# relay_shield3a.net
KiCad netlist of a schematic drawn in EAGLE
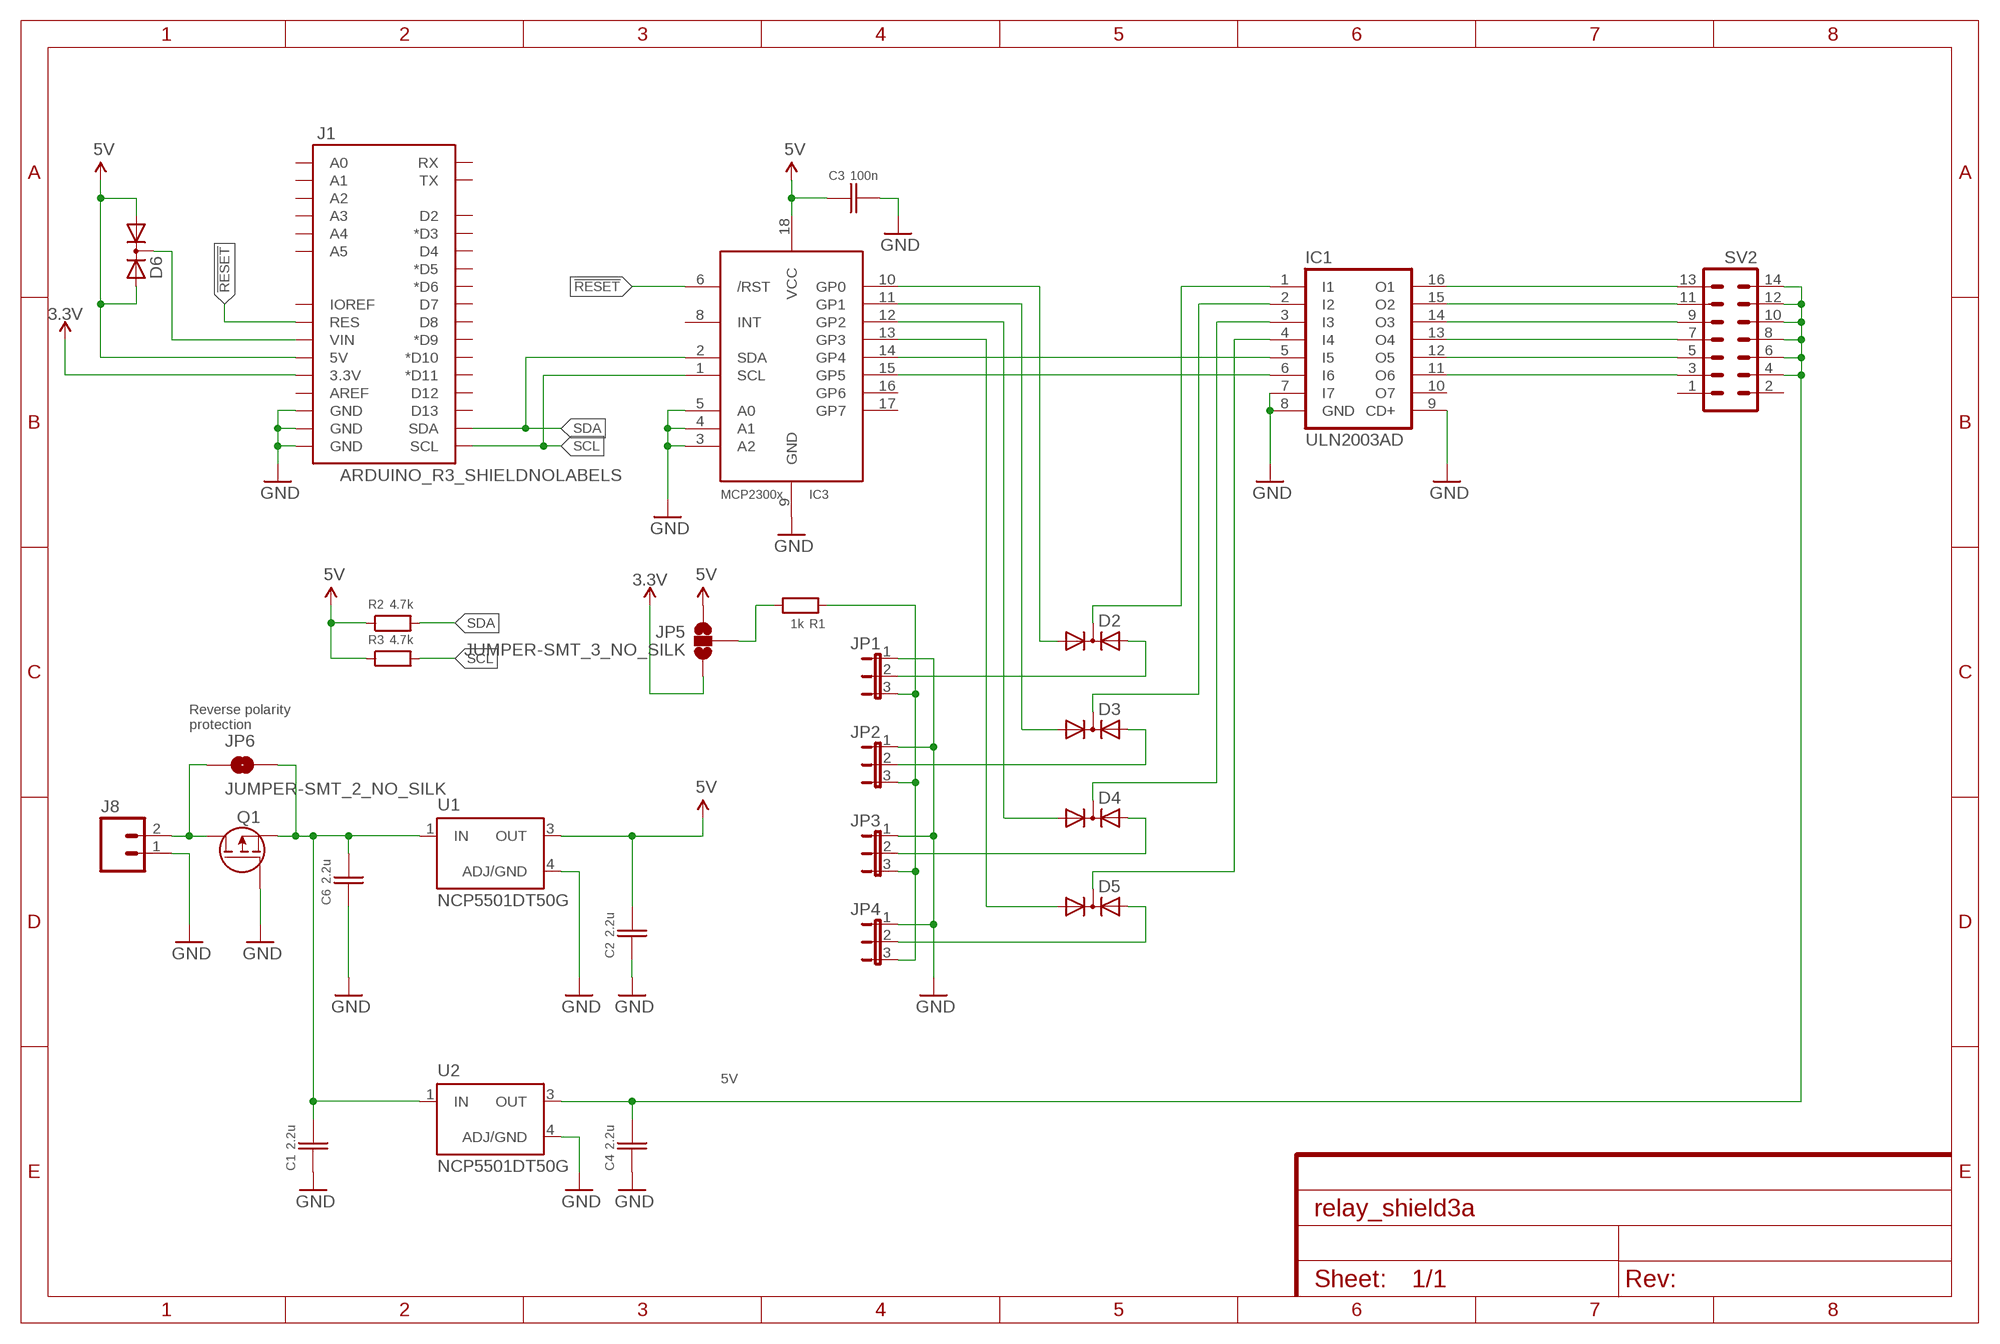
[diagram p0: schematic, sheet 1]

(export (version "E")
  (design (tool "Eeschema 10.0.6"))
  (components
    (comp (ref "C1")
      (value "2.2u")
      (footprint "eagle-import:C1206")
      (libsource (lib "eagle-import") (part "CAPACITOR_NPOL-1206"))
    )
    (comp (ref "C2")
      (value "2.2u")
      (footprint "eagle-import:C1206")
      (libsource (lib "eagle-import") (part "CAPACITOR_NPOL-1206"))
    )
    (comp (ref "C3")
      (value "100n")
      (footprint "eagle-import:C603")
      (libsource (lib "eagle-import") (part "CAPACITOR_NPOL-0603"))
    )
    (comp (ref "C4")
      (value "2.2u")
      (footprint "eagle-import:C1206")
      (libsource (lib "eagle-import") (part "CAPACITOR_NPOL-1206"))
    )
    (comp (ref "C6")
      (value "2.2u")
      (footprint "eagle-import:C1206")
      (libsource (lib "eagle-import") (part "CAPACITOR_NPOL-1206"))
    )
    (comp (ref "D2")
      (value "DIODE-2AC|CASOT23")
      (footprint "eagle-import:SOT23")
      (libsource (lib "eagle-import") (part "DIODE-2AC|CASOT23"))
    )
    (comp (ref "D3")
      (value "DIODE-2AC|CASOT23")
      (footprint "eagle-import:SOT23")
      (libsource (lib "eagle-import") (part "DIODE-2AC|CASOT23"))
    )
    (comp (ref "D4")
      (value "DIODE-2AC|CASOT23")
      (footprint "eagle-import:SOT23")
      (libsource (lib "eagle-import") (part "DIODE-2AC|CASOT23"))
    )
    (comp (ref "D5")
      (value "DIODE-2AC|CASOT23")
      (footprint "eagle-import:SOT23")
      (libsource (lib "eagle-import") (part "DIODE-2AC|CASOT23"))
    )
    (comp (ref "D6")
      (value "DIODE-2AC|CASOT23")
      (footprint "eagle-import:SOT23")
      (libsource (lib "eagle-import") (part "DIODE-2AC|CASOT23"))
    )
    (comp (ref "IC1")
      (value "ULN2003AD")
      (footprint "eagle-import:SO16")
      (libsource (lib "eagle-import") (part "ULN2003AD"))
    )
    (comp (ref "IC3")
      (value "MCP23008/SO")
      (footprint "eagle-import:SO18W")
      (libsource (lib "eagle-import") (part "MCP23008/SO"))
    )
    (comp (ref "J1")
      (value "ARDUINO_R3_SHIELDNOLABELS")
      (footprint "eagle-import:UNO_R3_SHIELD_NOLABELS")
      (libsource (lib "eagle-import") (part "ARDUINO_R3_SHIELDNOLABELS"))
    )
    (comp (ref "J8")
      (value "M023.5MM")
      (footprint "eagle-import:SCREWTERMINAL-3.5MM-2")
      (libsource (lib "eagle-import") (part "M023.5MM"))
    )
    (comp (ref "JP1")
      (value "JP2E")
      (footprint "eagle-import:JP2")
      (libsource (lib "eagle-import") (part "JP2E"))
    )
    (comp (ref "JP2")
      (value "JP2E")
      (footprint "eagle-import:JP2")
      (libsource (lib "eagle-import") (part "JP2E"))
    )
    (comp (ref "JP3")
      (value "JP2E")
      (footprint "eagle-import:JP2")
      (libsource (lib "eagle-import") (part "JP2E"))
    )
    (comp (ref "JP4")
      (value "JP2E")
      (footprint "eagle-import:JP2")
      (libsource (lib "eagle-import") (part "JP2E"))
    )
    (comp (ref "JP5")
      (value "JUMPER-SMT_3_NO_SILK")
      (footprint "eagle-import:SMT-JUMPER_3_NO_SILK")
      (libsource (lib "eagle-import") (part "JUMPER-SMT_3_NO_SILK"))
    )
    (comp (ref "JP6")
      (value "JUMPER-SMT_2_NO_SILK")
      (footprint "eagle-import:SMT-JUMPER_2_NO_SILK")
      (libsource (lib "eagle-import") (part "JUMPER-SMT_2_NO_SILK"))
    )
    (comp (ref "Q1")
      (value "MOSFET-P-SOT23-3")
      (footprint "eagle-import:SOT23-3")
      (libsource (lib "eagle-import") (part "MOSFET-P-SOT23-3"))
    )
    (comp (ref "R1")
      (value "1k")
      (footprint "eagle-import:R0603")
      (libsource (lib "eagle-import") (part "RESISTOR-0603"))
    )
    (comp (ref "R2")
      (value "4.7k")
      (footprint "eagle-import:R0603")
      (libsource (lib "eagle-import") (part "RESISTOR-0603"))
    )
    (comp (ref "R3")
      (value "4.7k")
      (footprint "eagle-import:R0603")
      (libsource (lib "eagle-import") (part "RESISTOR-0603"))
    )
    (comp (ref "SV2")
      (value "ML14L")
      (footprint "eagle-import:ML14L")
      (libsource (lib "eagle-import") (part "ML14L"))
    )
    (comp (ref "U1")
      (value "NCP5501DT50G")
      (footprint "eagle-import:DPAK")
      (libsource (lib "eagle-import") (part "VREG-3PIN-DPAK"))
    )
    (comp (ref "U2")
      (value "NCP5501DT50G")
      (footprint "eagle-import:DPAK")
      (libsource (lib "eagle-import") (part "VREG-3PIN-DPAK"))
    )
  )
  (nets
    (net (code "1") (name "/~{RESET}") (class "Default")
      (node (ref "IC3") (pin "6") (pinfunction "/RST_6") (pintype "input"))
      (node (ref "J1") (pin "RES") (pinfunction "RES_RES") (pintype "bidirectional"))
    )
    (net (code "2") (name "3.3V") (class "Default")
      (node (ref "J1") (pin "3.3V") (pinfunction "3.3V_3.3V") (pintype "bidirectional"))
      (node (ref "JP5") (pin "3") (pinfunction "3_3") (pintype "passive"))
    )
    (net (code "3") (name "5V") (class "Default")
      (node (ref "C2") (pin "2") (pinfunction "2_2") (pintype "passive"))
      (node (ref "C3") (pin "1") (pinfunction "1_1") (pintype "passive"))
      (node (ref "D6") (pin "1") (pinfunction "A1_1") (pintype "passive"))
      (node (ref "D6") (pin "2") (pinfunction "A2_2") (pintype "passive"))
      (node (ref "IC3") (pin "18") (pinfunction "VCC_18") (pintype "power_in"))
      (node (ref "J1") (pin "5V") (pinfunction "5V_5V") (pintype "bidirectional"))
      (node (ref "JP5") (pin "1") (pinfunction "1_1") (pintype "passive"))
      (node (ref "R2") (pin "1") (pinfunction "1_1") (pintype "passive"))
      (node (ref "R3") (pin "1") (pinfunction "1_1") (pintype "passive"))
      (node (ref "U1") (pin "3") (pinfunction "OUT_3") (pintype "bidirectional"))
    )
    (net (code "4") (name "GND") (class "Default")
      (node (ref "C1") (pin "1") (pinfunction "1_1") (pintype "passive"))
      (node (ref "C2") (pin "1") (pinfunction "1_1") (pintype "passive"))
      (node (ref "C3") (pin "2") (pinfunction "2_2") (pintype "passive"))
      (node (ref "C4") (pin "1") (pinfunction "1_1") (pintype "passive"))
      (node (ref "C6") (pin "1") (pinfunction "1_1") (pintype "passive"))
      (node (ref "IC1") (pin "7") (pinfunction "I7_7") (pintype "input"))
      (node (ref "IC1") (pin "8") (pinfunction "GND_8") (pintype "power_in"))
      (node (ref "IC1") (pin "9") (pinfunction "CD+_9") (pintype "passive"))
      (node (ref "IC3") (pin "3") (pinfunction "A2_3") (pintype "input"))
      (node (ref "IC3") (pin "4") (pinfunction "A1_4") (pintype "input"))
      (node (ref "IC3") (pin "5") (pinfunction "A0_5") (pintype "input"))
      (node (ref "IC3") (pin "9") (pinfunction "GND_9") (pintype "power_in"))
      (node (ref "J1") (pin "GND@0") (pinfunction "GND_GND@0") (pintype "bidirectional"))
      (node (ref "J1") (pin "GND@1") (pinfunction "GND_GND@1") (pintype "bidirectional"))
      (node (ref "J1") (pin "GND@2") (pinfunction "GND_GND@2") (pintype "bidirectional"))
      (node (ref "J8") (pin "1") (pinfunction "1_1") (pintype "passive"))
      (node (ref "JP1") (pin "1") (pinfunction "1_1") (pintype "passive"))
      (node (ref "JP2") (pin "1") (pinfunction "1_1") (pintype "passive"))
      (node (ref "JP3") (pin "1") (pinfunction "1_1") (pintype "passive"))
      (node (ref "JP4") (pin "1") (pinfunction "1_1") (pintype "passive"))
      (node (ref "Q1") (pin "1") (pinfunction "G_1") (pintype "passive"))
      (node (ref "U1") (pin "4") (pinfunction "ADJ/GND_4") (pintype "bidirectional"))
      (node (ref "U2") (pin "4") (pinfunction "ADJ/GND_4") (pintype "bidirectional"))
    )
    (net (code "5") (name "Net-(D2-A1)") (class "Default")
      (node (ref "D2") (pin "1") (pinfunction "A1_1") (pintype "passive"))
      (node (ref "IC3") (pin "10") (pinfunction "GP0_10") (pintype "bidirectional"))
    )
    (net (code "6") (name "Net-(D2-A2)") (class "Default")
      (node (ref "D2") (pin "2") (pinfunction "A2_2") (pintype "passive"))
      (node (ref "JP1") (pin "2") (pinfunction "2_2") (pintype "passive"))
    )
    (net (code "7") (name "Net-(D2-C)") (class "Default")
      (node (ref "D2") (pin "3") (pinfunction "C_3") (pintype "passive"))
      (node (ref "IC1") (pin "1") (pinfunction "I1_1") (pintype "input"))
    )
    (net (code "8") (name "Net-(D3-A1)") (class "Default")
      (node (ref "D3") (pin "1") (pinfunction "A1_1") (pintype "passive"))
      (node (ref "IC3") (pin "11") (pinfunction "GP1_11") (pintype "bidirectional"))
    )
    (net (code "9") (name "Net-(D3-A2)") (class "Default")
      (node (ref "D3") (pin "2") (pinfunction "A2_2") (pintype "passive"))
      (node (ref "JP2") (pin "2") (pinfunction "2_2") (pintype "passive"))
    )
    (net (code "10") (name "Net-(D3-C)") (class "Default")
      (node (ref "D3") (pin "3") (pinfunction "C_3") (pintype "passive"))
      (node (ref "IC1") (pin "2") (pinfunction "I2_2") (pintype "input"))
    )
    (net (code "11") (name "Net-(D4-A1)") (class "Default")
      (node (ref "D4") (pin "1") (pinfunction "A1_1") (pintype "passive"))
      (node (ref "IC3") (pin "12") (pinfunction "GP2_12") (pintype "bidirectional"))
    )
    (net (code "12") (name "Net-(D4-A2)") (class "Default")
      (node (ref "D4") (pin "2") (pinfunction "A2_2") (pintype "passive"))
      (node (ref "JP3") (pin "2") (pinfunction "2_2") (pintype "passive"))
    )
    (net (code "13") (name "Net-(D4-C)") (class "Default")
      (node (ref "D4") (pin "3") (pinfunction "C_3") (pintype "passive"))
      (node (ref "IC1") (pin "3") (pinfunction "I3_3") (pintype "input"))
    )
    (net (code "14") (name "Net-(D5-A1)") (class "Default")
      (node (ref "D5") (pin "1") (pinfunction "A1_1") (pintype "passive"))
      (node (ref "IC3") (pin "13") (pinfunction "GP3_13") (pintype "bidirectional"))
    )
    (net (code "15") (name "Net-(D5-A2)") (class "Default")
      (node (ref "D5") (pin "2") (pinfunction "A2_2") (pintype "passive"))
      (node (ref "JP4") (pin "2") (pinfunction "2_2") (pintype "passive"))
    )
    (net (code "16") (name "Net-(D5-C)") (class "Default")
      (node (ref "D5") (pin "3") (pinfunction "C_3") (pintype "passive"))
      (node (ref "IC1") (pin "4") (pinfunction "I4_4") (pintype "input"))
    )
    (net (code "17") (name "Net-(D6-C)") (class "Default")
      (node (ref "D6") (pin "3") (pinfunction "C_3") (pintype "passive"))
      (node (ref "J1") (pin "VIN") (pinfunction "VIN_VIN") (pintype "bidirectional"))
    )
    (net (code "18") (name "Net-(IC1-I5)") (class "Default")
      (node (ref "IC1") (pin "5") (pinfunction "I5_5") (pintype "input"))
      (node (ref "IC3") (pin "14") (pinfunction "GP4_14") (pintype "bidirectional"))
    )
    (net (code "19") (name "Net-(IC1-I6)") (class "Default")
      (node (ref "IC1") (pin "6") (pinfunction "I6_6") (pintype "input"))
      (node (ref "IC3") (pin "15") (pinfunction "GP5_15") (pintype "bidirectional"))
    )
    (net (code "20") (name "Net-(IC1-O1)") (class "Default")
      (node (ref "IC1") (pin "16") (pinfunction "O1_16") (pintype "open_collector"))
      (node (ref "SV2") (pin "13") (pinfunction "13_13") (pintype "passive"))
    )
    (net (code "21") (name "Net-(IC1-O2)") (class "Default")
      (node (ref "IC1") (pin "15") (pinfunction "O2_15") (pintype "open_collector"))
      (node (ref "SV2") (pin "11") (pinfunction "11_11") (pintype "passive"))
    )
    (net (code "22") (name "Net-(IC1-O3)") (class "Default")
      (node (ref "IC1") (pin "14") (pinfunction "O3_14") (pintype "open_collector"))
      (node (ref "SV2") (pin "9") (pinfunction "9_9") (pintype "passive"))
    )
    (net (code "23") (name "Net-(IC1-O4)") (class "Default")
      (node (ref "IC1") (pin "13") (pinfunction "O4_13") (pintype "open_collector"))
      (node (ref "SV2") (pin "7") (pinfunction "7_7") (pintype "passive"))
    )
    (net (code "24") (name "Net-(IC1-O5)") (class "Default")
      (node (ref "IC1") (pin "12") (pinfunction "O5_12") (pintype "open_collector"))
      (node (ref "SV2") (pin "5") (pinfunction "5_5") (pintype "passive"))
    )
    (net (code "25") (name "Net-(IC1-O6)") (class "Default")
      (node (ref "IC1") (pin "11") (pinfunction "O6_11") (pintype "open_collector"))
      (node (ref "SV2") (pin "3") (pinfunction "3_3") (pintype "passive"))
    )
    (net (code "26") (name "Net-(JP1-Pad3)") (class "Default")
      (node (ref "JP1") (pin "3") (pinfunction "3_3") (pintype "passive"))
      (node (ref "JP2") (pin "3") (pinfunction "3_3") (pintype "passive"))
      (node (ref "JP3") (pin "3") (pinfunction "3_3") (pintype "passive"))
      (node (ref "JP4") (pin "3") (pinfunction "3_3") (pintype "passive"))
      (node (ref "R1") (pin "1") (pinfunction "1_1") (pintype "passive"))
    )
    (net (code "27") (name "Net-(JP5-Pad2)") (class "Default")
      (node (ref "JP5") (pin "2") (pinfunction "2_2") (pintype "passive"))
      (node (ref "R1") (pin "2") (pinfunction "2_2") (pintype "passive"))
    )
    (net (code "28") (name "Net-(Q1-D)") (class "Default")
      (node (ref "J8") (pin "2") (pinfunction "2_2") (pintype "passive"))
      (node (ref "JP6") (pin "1") (pinfunction "1_1") (pintype "passive"))
      (node (ref "Q1") (pin "3") (pinfunction "D_3") (pintype "passive"))
    )
    (net (code "29") (name "Net-(Q1-S)") (class "Default")
      (node (ref "C1") (pin "2") (pinfunction "2_2") (pintype "passive"))
      (node (ref "C6") (pin "2") (pinfunction "2_2") (pintype "passive"))
      (node (ref "JP6") (pin "2") (pinfunction "2_2") (pintype "passive"))
      (node (ref "Q1") (pin "2") (pinfunction "S_2") (pintype "passive"))
      (node (ref "U1") (pin "1") (pinfunction "IN_1") (pintype "bidirectional"))
      (node (ref "U2") (pin "1") (pinfunction "IN_1") (pintype "bidirectional"))
    )
    (net (code "30") (name "Net-(U2-OUT)") (class "Default")
      (node (ref "C4") (pin "2") (pinfunction "2_2") (pintype "passive"))
      (node (ref "SV2") (pin "10") (pinfunction "10_10") (pintype "passive"))
      (node (ref "SV2") (pin "12") (pinfunction "12_12") (pintype "passive"))
      (node (ref "SV2") (pin "14") (pinfunction "14_14") (pintype "passive"))
      (node (ref "SV2") (pin "4") (pinfunction "4_4") (pintype "passive"))
      (node (ref "SV2") (pin "6") (pinfunction "6_6") (pintype "passive"))
      (node (ref "SV2") (pin "8") (pinfunction "8_8") (pintype "passive"))
      (node (ref "U2") (pin "3") (pinfunction "OUT_3") (pintype "bidirectional"))
    )
    (net (code "31") (name "SCL") (class "Default")
      (node (ref "IC3") (pin "1") (pinfunction "SCL_1") (pintype "bidirectional"))
      (node (ref "J1") (pin "SCL") (pinfunction "SCL_SCL") (pintype "bidirectional"))
      (node (ref "R3") (pin "2") (pinfunction "2_2") (pintype "passive"))
    )
    (net (code "32") (name "SDA") (class "Default")
      (node (ref "IC3") (pin "2") (pinfunction "SDA_2") (pintype "bidirectional"))
      (node (ref "J1") (pin "SDA") (pinfunction "SDA_SDA") (pintype "bidirectional"))
      (node (ref "R2") (pin "2") (pinfunction "2_2") (pintype "passive"))
    )
    (net (code "33") (name "unconnected-(IC1-O7-Pad10)") (class "Default")
      (node (ref "IC1") (pin "10") (pinfunction "O7_10") (pintype "open_collector"))
    )
    (net (code "34") (name "unconnected-(IC3-GP6-Pad16)") (class "Default")
      (node (ref "IC3") (pin "16") (pinfunction "GP6_16") (pintype "bidirectional"))
    )
    (net (code "35") (name "unconnected-(IC3-GP7-Pad17)") (class "Default")
      (node (ref "IC3") (pin "17") (pinfunction "GP7_17") (pintype "bidirectional"))
    )
    (net (code "36") (name "unconnected-(IC3-INT-Pad8)") (class "Default")
      (node (ref "IC3") (pin "8") (pinfunction "INT_8") (pintype "output"))
    )
    (net (code "37") (name "unconnected-(J1-*D3-PadD3)") (class "Default")
      (node (ref "J1") (pin "D3") (pinfunction "*D3_D3") (pintype "bidirectional"))
    )
    (net (code "38") (name "unconnected-(J1-*D5-PadD5)") (class "Default")
      (node (ref "J1") (pin "D5") (pinfunction "*D5_D5") (pintype "bidirectional"))
    )
    (net (code "39") (name "unconnected-(J1-*D6-PadD6)") (class "Default")
      (node (ref "J1") (pin "D6") (pinfunction "*D6_D6") (pintype "bidirectional"))
    )
    (net (code "40") (name "unconnected-(J1-*D9-PadD9)") (class "Default")
      (node (ref "J1") (pin "D9") (pinfunction "*D9_D9") (pintype "bidirectional"))
    )
    (net (code "41") (name "unconnected-(J1-*D10-PadD10)") (class "Default")
      (node (ref "J1") (pin "D10") (pinfunction "*D10_D10") (pintype "bidirectional"))
    )
    (net (code "42") (name "unconnected-(J1-*D11-PadD11)") (class "Default")
      (node (ref "J1") (pin "D11") (pinfunction "*D11_D11") (pintype "bidirectional"))
    )
    (net (code "43") (name "unconnected-(J1-PadA0)") (class "Default")
      (node (ref "J1") (pin "A0") (pinfunction "A0_A0") (pintype "bidirectional"))
    )
    (net (code "44") (name "unconnected-(J1-PadA1)") (class "Default")
      (node (ref "J1") (pin "A1") (pinfunction "A1_A1") (pintype "bidirectional"))
    )
    (net (code "45") (name "unconnected-(J1-PadA2)") (class "Default")
      (node (ref "J1") (pin "A2") (pinfunction "A2_A2") (pintype "bidirectional"))
    )
    (net (code "46") (name "unconnected-(J1-PadA3)") (class "Default")
      (node (ref "J1") (pin "A3") (pinfunction "A3_A3") (pintype "bidirectional"))
    )
    (net (code "47") (name "unconnected-(J1-PadA4)") (class "Default")
      (node (ref "J1") (pin "A4") (pinfunction "A4_A4") (pintype "bidirectional"))
    )
    (net (code "48") (name "unconnected-(J1-PadA5)") (class "Default")
      (node (ref "J1") (pin "A5") (pinfunction "A5_A5") (pintype "bidirectional"))
    )
    (net (code "49") (name "unconnected-(J1-PadAREF)") (class "Default")
      (node (ref "J1") (pin "AREF") (pinfunction "AREF_AREF") (pintype "bidirectional"))
    )
    (net (code "50") (name "unconnected-(J1-PadD2)") (class "Default")
      (node (ref "J1") (pin "D2") (pinfunction "D2_D2") (pintype "bidirectional"))
    )
    (net (code "51") (name "unconnected-(J1-PadD4)") (class "Default")
      (node (ref "J1") (pin "D4") (pinfunction "D4_D4") (pintype "bidirectional"))
    )
    (net (code "52") (name "unconnected-(J1-PadD7)") (class "Default")
      (node (ref "J1") (pin "D7") (pinfunction "D7_D7") (pintype "bidirectional"))
    )
    (net (code "53") (name "unconnected-(J1-PadD8)") (class "Default")
      (node (ref "J1") (pin "D8") (pinfunction "D8_D8") (pintype "bidirectional"))
    )
    (net (code "54") (name "unconnected-(J1-PadD12)") (class "Default")
      (node (ref "J1") (pin "D12") (pinfunction "D12_D12") (pintype "bidirectional"))
    )
    (net (code "55") (name "unconnected-(J1-PadD13)") (class "Default")
      (node (ref "J1") (pin "D13") (pinfunction "D13_D13") (pintype "bidirectional"))
    )
    (net (code "56") (name "unconnected-(J1-PadIOREF)") (class "Default")
      (node (ref "J1") (pin "IOREF") (pinfunction "IOREF_IOREF") (pintype "bidirectional"))
    )
    (net (code "57") (name "unconnected-(J1-PadRX)") (class "Default")
      (node (ref "J1") (pin "RX") (pinfunction "RX_RX") (pintype "bidirectional"))
    )
    (net (code "58") (name "unconnected-(J1-PadTX)") (class "Default")
      (node (ref "J1") (pin "TX") (pinfunction "TX_TX") (pintype "bidirectional"))
    )
    (net (code "59") (name "unconnected-(SV2-Pad1)") (class "Default")
      (node (ref "SV2") (pin "1") (pinfunction "1_1") (pintype "passive"))
    )
    (net (code "60") (name "unconnected-(SV2-Pad2)") (class "Default")
      (node (ref "SV2") (pin "2") (pinfunction "2_2") (pintype "passive"))
    )
  )
)
